# circle_humidity.net
KiCad netlist of a schematic drawn in EAGLE
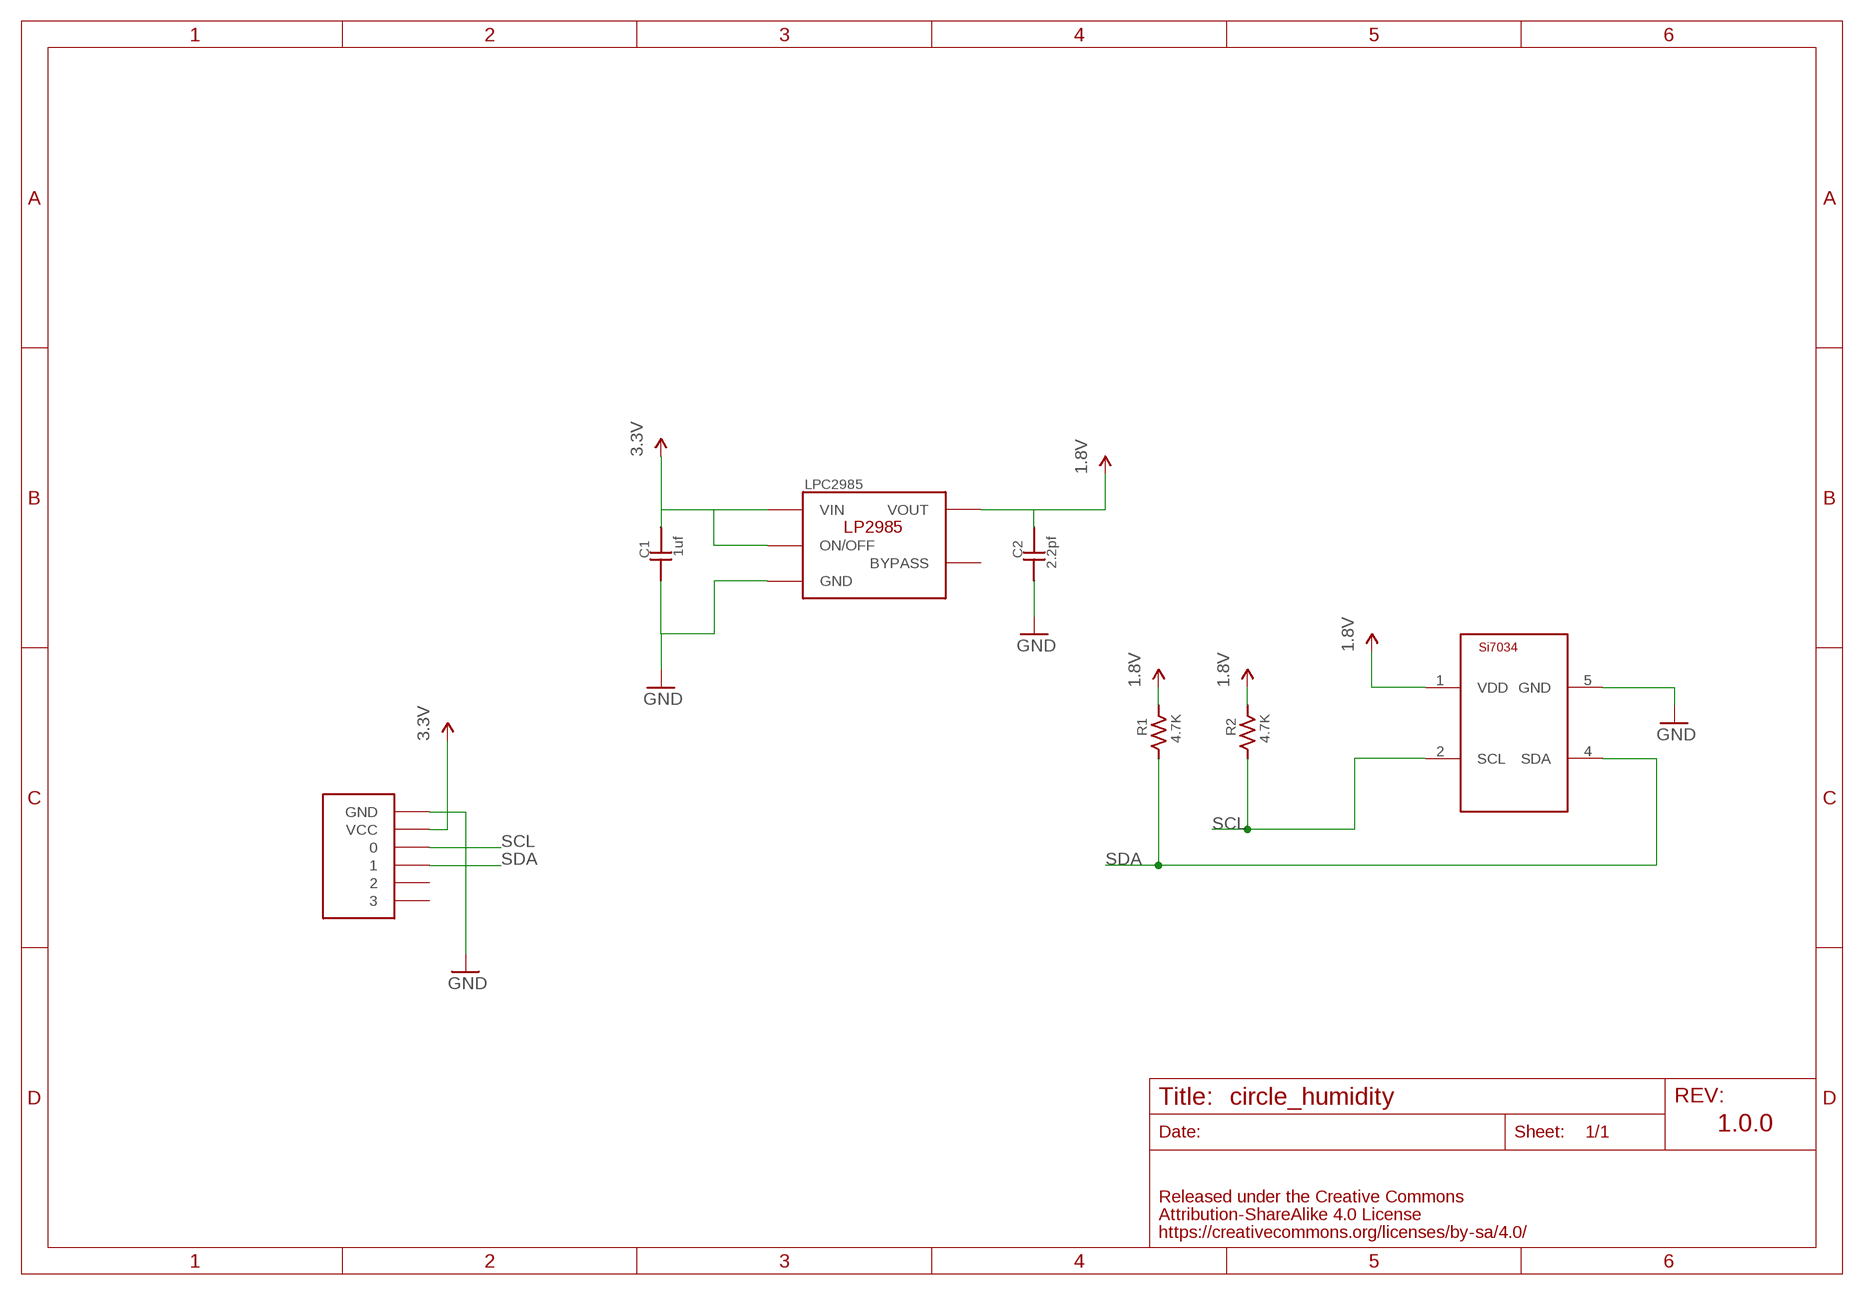
[diagram p0: schematic, sheet 1]

(export (version "E")
  (design (tool "Eeschema 10.0.6"))
  (components
    (comp (ref "C1")
      (value "1uf")
      (footprint "eagle-import:0402")
      (libsource (lib "eagle-import") (part "CAPACITOR0402"))
    )
    (comp (ref "C2")
      (value "2.2pf")
      (footprint "eagle-import:0402")
      (libsource (lib "eagle-import") (part "CAPACITOR0402"))
    )
    (comp (ref "LPC2985")
      (value "TI-LP2985-18DBVT")
      (footprint "eagle-import:TI-LP2985")
      (libsource (lib "eagle-import") (part "TI-LP2985-18DBVT"))
    )
    (comp (ref "R1")
      (value "4.7K")
      (footprint "eagle-import:0402")
      (libsource (lib "eagle-import") (part "RESISTOR-0402"))
    )
    (comp (ref "R2")
      (value "4.7K")
      (footprint "eagle-import:0402")
      (libsource (lib "eagle-import") (part "RESISTOR-0402"))
    )
    (comp (ref "U$5")
      (value "FABO-NANO")
      (footprint "eagle-import:FABO-NANO")
      (libsource (lib "eagle-import") (part "FABO-NANO"))
    )
    (comp (ref "U$6")
      (value "SILICONLABS-SI7034")
      (footprint "eagle-import:SILICONLABS-SI7034")
      (libsource (lib "eagle-import") (part "SILICONLABS-SI7034"))
    )
  )
  (nets
    (net (code "1") (name "/SCL") (class "Default")
      (node (ref "R2") (pin "P$1") (pinfunction "1_P$1") (pintype "bidirectional"))
      (node (ref "U$5") (pin "0") (pinfunction "0_0") (pintype "bidirectional"))
      (node (ref "U$6") (pin "2") (pinfunction "SCL_2") (pintype "bidirectional"))
    )
    (net (code "2") (name "/SDA") (class "Default")
      (node (ref "R1") (pin "P$1") (pinfunction "1_P$1") (pintype "bidirectional"))
      (node (ref "U$5") (pin "1") (pinfunction "1_1") (pintype "bidirectional"))
      (node (ref "U$6") (pin "4") (pinfunction "SDA_4") (pintype "bidirectional"))
    )
    (net (code "3") (name "1.8V") (class "Default")
      (node (ref "C2") (pin "P$2") (pinfunction "2_P$2") (pintype "passive"))
      (node (ref "LPC2985") (pin "5") (pinfunction "VOUT_5") (pintype "output"))
      (node (ref "R1") (pin "P$2") (pinfunction "2_P$2") (pintype "bidirectional"))
      (node (ref "R2") (pin "P$2") (pinfunction "2_P$2") (pintype "bidirectional"))
      (node (ref "U$6") (pin "1") (pinfunction "VDD_1") (pintype "bidirectional"))
    )
    (net (code "4") (name "3.3V") (class "Default")
      (node (ref "C1") (pin "P$2") (pinfunction "2_P$2") (pintype "passive"))
      (node (ref "LPC2985") (pin "1") (pinfunction "VIN_1") (pintype "input"))
      (node (ref "LPC2985") (pin "3") (pinfunction "ON/OFF_3") (pintype "input"))
      (node (ref "U$5") (pin "VCC") (pinfunction "VCC_VCC") (pintype "bidirectional"))
    )
    (net (code "5") (name "GND") (class "Default")
      (node (ref "C1") (pin "P$1") (pinfunction "1_P$1") (pintype "passive"))
      (node (ref "C2") (pin "P$1") (pinfunction "1_P$1") (pintype "passive"))
      (node (ref "LPC2985") (pin "2") (pinfunction "GND_2") (pintype "power_in"))
      (node (ref "U$5") (pin "GND") (pinfunction "GND_GND") (pintype "bidirectional"))
      (node (ref "U$6") (pin "5") (pinfunction "GND_5") (pintype "bidirectional"))
    )
    (net (code "6") (name "unconnected-(LPC2985-BYPASS-Pad4)") (class "Default")
      (node (ref "LPC2985") (pin "4") (pinfunction "BYPASS_4") (pintype "bidirectional"))
    )
    (net (code "7") (name "unconnected-(U$5-Pad2)") (class "Default")
      (node (ref "U$5") (pin "2") (pinfunction "2_2") (pintype "bidirectional"))
    )
    (net (code "8") (name "unconnected-(U$5-Pad3)") (class "Default")
      (node (ref "U$5") (pin "3") (pinfunction "3_3") (pintype "bidirectional"))
    )
  )
)
